# EEPROM.net
KiCad netlist of a schematic drawn in Altium Designer
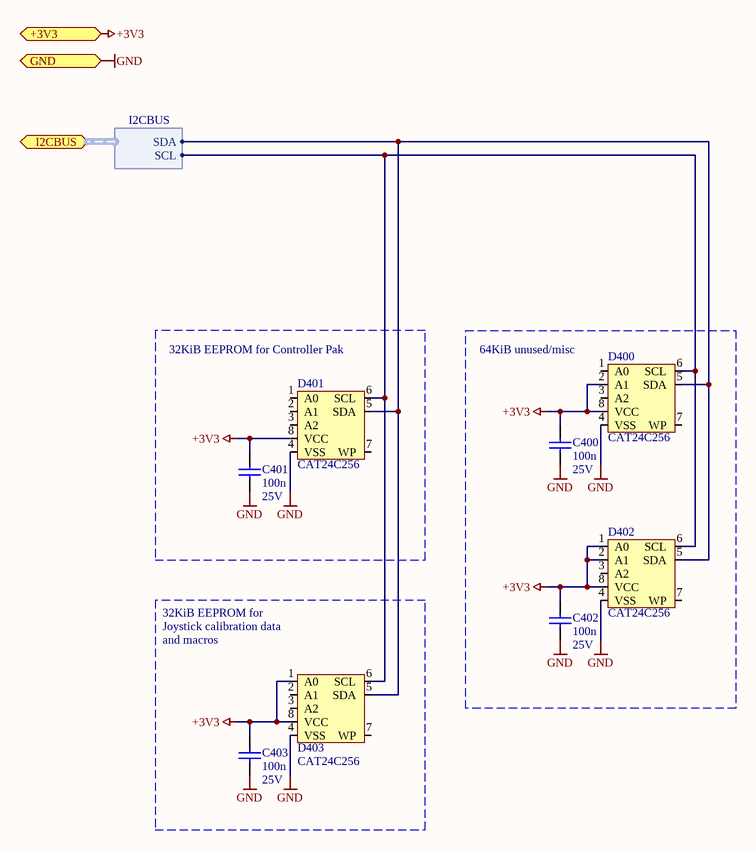
[diagram p0: EEPROM.SchDoc]

(export (version "E")
  (design (tool "Eeschema 10.0.6"))
  (components
    (comp (ref "C400")
      (value "100n")
      (footprint "SMD_CAP_0402")
      (description "0.1µF ±10% 25V Ceramic Capacitor X7R 0402 (1005 Metric)")
      (fields (field (name "VALUE2") "25V") (field (name "Comment") "C_SMD_CER_100N_25V_10%_X7R_0402"))
      (libsource (lib "AM") (part "C_SMD_CER_100N_25V_10%_X7R_0402"))
    )
    (comp (ref "C401")
      (value "100n")
      (footprint "SMD_CAP_0402")
      (description "0.1µF ±10% 25V Ceramic Capacitor X7R 0402 (1005 Metric)")
      (fields (field (name "VALUE2") "25V") (field (name "Comment") "C_SMD_CER_100N_25V_10%_X7R_0402"))
      (libsource (lib "AM") (part "C_SMD_CER_100N_25V_10%_X7R_0402"))
    )
    (comp (ref "C402")
      (value "100n")
      (footprint "SMD_CAP_0402")
      (description "0.1µF ±10% 25V Ceramic Capacitor X7R 0402 (1005 Metric)")
      (fields (field (name "VALUE2") "25V") (field (name "Comment") "C_SMD_CER_100N_25V_10%_X7R_0402"))
      (libsource (lib "AM") (part "C_SMD_CER_100N_25V_10%_X7R_0402"))
    )
    (comp (ref "C403")
      (value "100n")
      (footprint "SMD_CAP_0402")
      (description "0.1µF ±10% 25V Ceramic Capacitor X7R 0402 (1005 Metric)")
      (fields (field (name "VALUE2") "25V") (field (name "Comment") "C_SMD_CER_100N_25V_10%_X7R_0402"))
      (libsource (lib "AM") (part "C_SMD_CER_100N_25V_10%_X7R_0402"))
    )
    (comp (ref "D400")
      (value "D_CAT24C256_EEPROM_TSSOP-8")
      (footprint "SMD_TSSOP_8")
      (description "IC EEPROM 256K I2C 1MHZ 8TSSOP")
      (fields (field (name "TYPE") "CAT24C256"))
      (libsource (lib "AM") (part "D_CAT24C256_EEPROM_TSSOP-8"))
    )
    (comp (ref "D401")
      (value "D_CAT24C256_EEPROM_TSSOP-8")
      (footprint "SMD_TSSOP_8")
      (description "IC EEPROM 256K I2C 1MHZ 8TSSOP")
      (fields (field (name "TYPE") "CAT24C256"))
      (libsource (lib "AM") (part "D_CAT24C256_EEPROM_TSSOP-8"))
    )
    (comp (ref "D402")
      (value "D_CAT24C256_EEPROM_TSSOP-8")
      (footprint "SMD_TSSOP_8")
      (description "IC EEPROM 256K I2C 1MHZ 8TSSOP")
      (fields (field (name "TYPE") "CAT24C256"))
      (libsource (lib "AM") (part "D_CAT24C256_EEPROM_TSSOP-8"))
    )
    (comp (ref "D403")
      (value "D_CAT24C256_EEPROM_TSSOP-8")
      (footprint "SMD_TSSOP_8")
      (description "IC EEPROM 256K I2C 1MHZ 8TSSOP")
      (fields (field (name "TYPE") "CAT24C256"))
      (libsource (lib "AM") (part "D_CAT24C256_EEPROM_TSSOP-8"))
    )
  )
  (nets
    (net (code "2") (name "+3V3") (class "Default")
      (node (ref "C400") (pin "2") (pinfunction "2_2") (pintype "passive"))
      (node (ref "C401") (pin "2") (pinfunction "2_2") (pintype "passive"))
      (node (ref "C402") (pin "2") (pinfunction "2_2") (pintype "passive"))
      (node (ref "C403") (pin "2") (pinfunction "2_2") (pintype "passive"))
      (node (ref "D400") (pin "2") (pinfunction "A1_2") (pintype "passive"))
      (node (ref "D400") (pin "8") (pinfunction "VCC_8") (pintype "passive"))
      (node (ref "D401") (pin "8") (pinfunction "VCC_8") (pintype "passive"))
      (node (ref "D402") (pin "1") (pinfunction "A0_1") (pintype "passive"))
      (node (ref "D402") (pin "2") (pinfunction "A1_2") (pintype "passive"))
      (node (ref "D402") (pin "8") (pinfunction "VCC_8") (pintype "passive"))
      (node (ref "D403") (pin "1") (pinfunction "A0_1") (pintype "passive"))
      (node (ref "D403") (pin "8") (pinfunction "VCC_8") (pintype "passive"))
    )
    (net (code "4") (name "GND") (class "Default")
      (node (ref "C400") (pin "1") (pinfunction "1_1") (pintype "passive"))
      (node (ref "C401") (pin "1") (pinfunction "1_1") (pintype "passive"))
      (node (ref "C402") (pin "1") (pinfunction "1_1") (pintype "passive"))
      (node (ref "C403") (pin "1") (pinfunction "1_1") (pintype "passive"))
      (node (ref "D400") (pin "4") (pinfunction "VSS_4") (pintype "passive"))
      (node (ref "D401") (pin "4") (pinfunction "VSS_4") (pintype "passive"))
      (node (ref "D402") (pin "4") (pinfunction "VSS_4") (pintype "passive"))
      (node (ref "D403") (pin "4") (pinfunction "VSS_4") (pintype "passive"))
    )
    (net (code "5") (name "Net-(D400-SCL)") (class "Default")
      (node (ref "D400") (pin "6") (pinfunction "SCL_6") (pintype "passive"))
      (node (ref "D401") (pin "6") (pinfunction "SCL_6") (pintype "passive"))
      (node (ref "D402") (pin "6") (pinfunction "SCL_6") (pintype "passive"))
      (node (ref "D403") (pin "6") (pinfunction "SCL_6") (pintype "passive"))
    )
    (net (code "6") (name "Net-(D400-SDA)") (class "Default")
      (node (ref "D400") (pin "5") (pinfunction "SDA_5") (pintype "passive"))
      (node (ref "D401") (pin "5") (pinfunction "SDA_5") (pintype "passive"))
      (node (ref "D402") (pin "5") (pinfunction "SDA_5") (pintype "passive"))
      (node (ref "D403") (pin "5") (pinfunction "SDA_5") (pintype "passive"))
    )
    (net (code "7") (name "unconnected-(D400-A0-Pad1)") (class "Default")
      (node (ref "D400") (pin "1") (pinfunction "A0_1") (pintype "passive"))
    )
    (net (code "8") (name "unconnected-(D400-A2-Pad3)") (class "Default")
      (node (ref "D400") (pin "3") (pinfunction "A2_3") (pintype "passive"))
    )
    (net (code "9") (name "unconnected-(D400-WP-Pad7)") (class "Default")
      (node (ref "D400") (pin "7") (pinfunction "WP_7") (pintype "passive"))
    )
    (net (code "10") (name "unconnected-(D401-A0-Pad1)") (class "Default")
      (node (ref "D401") (pin "1") (pinfunction "A0_1") (pintype "passive"))
    )
    (net (code "11") (name "unconnected-(D401-A1-Pad2)") (class "Default")
      (node (ref "D401") (pin "2") (pinfunction "A1_2") (pintype "passive"))
    )
    (net (code "12") (name "unconnected-(D401-A2-Pad3)") (class "Default")
      (node (ref "D401") (pin "3") (pinfunction "A2_3") (pintype "passive"))
    )
    (net (code "13") (name "unconnected-(D401-WP-Pad7)") (class "Default")
      (node (ref "D401") (pin "7") (pinfunction "WP_7") (pintype "passive"))
    )
    (net (code "14") (name "unconnected-(D402-A2-Pad3)") (class "Default")
      (node (ref "D402") (pin "3") (pinfunction "A2_3") (pintype "passive"))
    )
    (net (code "15") (name "unconnected-(D402-WP-Pad7)") (class "Default")
      (node (ref "D402") (pin "7") (pinfunction "WP_7") (pintype "passive"))
    )
    (net (code "16") (name "unconnected-(D403-A1-Pad2)") (class "Default")
      (node (ref "D403") (pin "2") (pinfunction "A1_2") (pintype "passive"))
    )
    (net (code "17") (name "unconnected-(D403-A2-Pad3)") (class "Default")
      (node (ref "D403") (pin "3") (pinfunction "A2_3") (pintype "passive"))
    )
    (net (code "18") (name "unconnected-(D403-WP-Pad7)") (class "Default")
      (node (ref "D403") (pin "7") (pinfunction "WP_7") (pintype "passive"))
    )
  )
)
